# Fuel_Gauge.net
KiCad netlist of a schematic drawn in Altium Designer
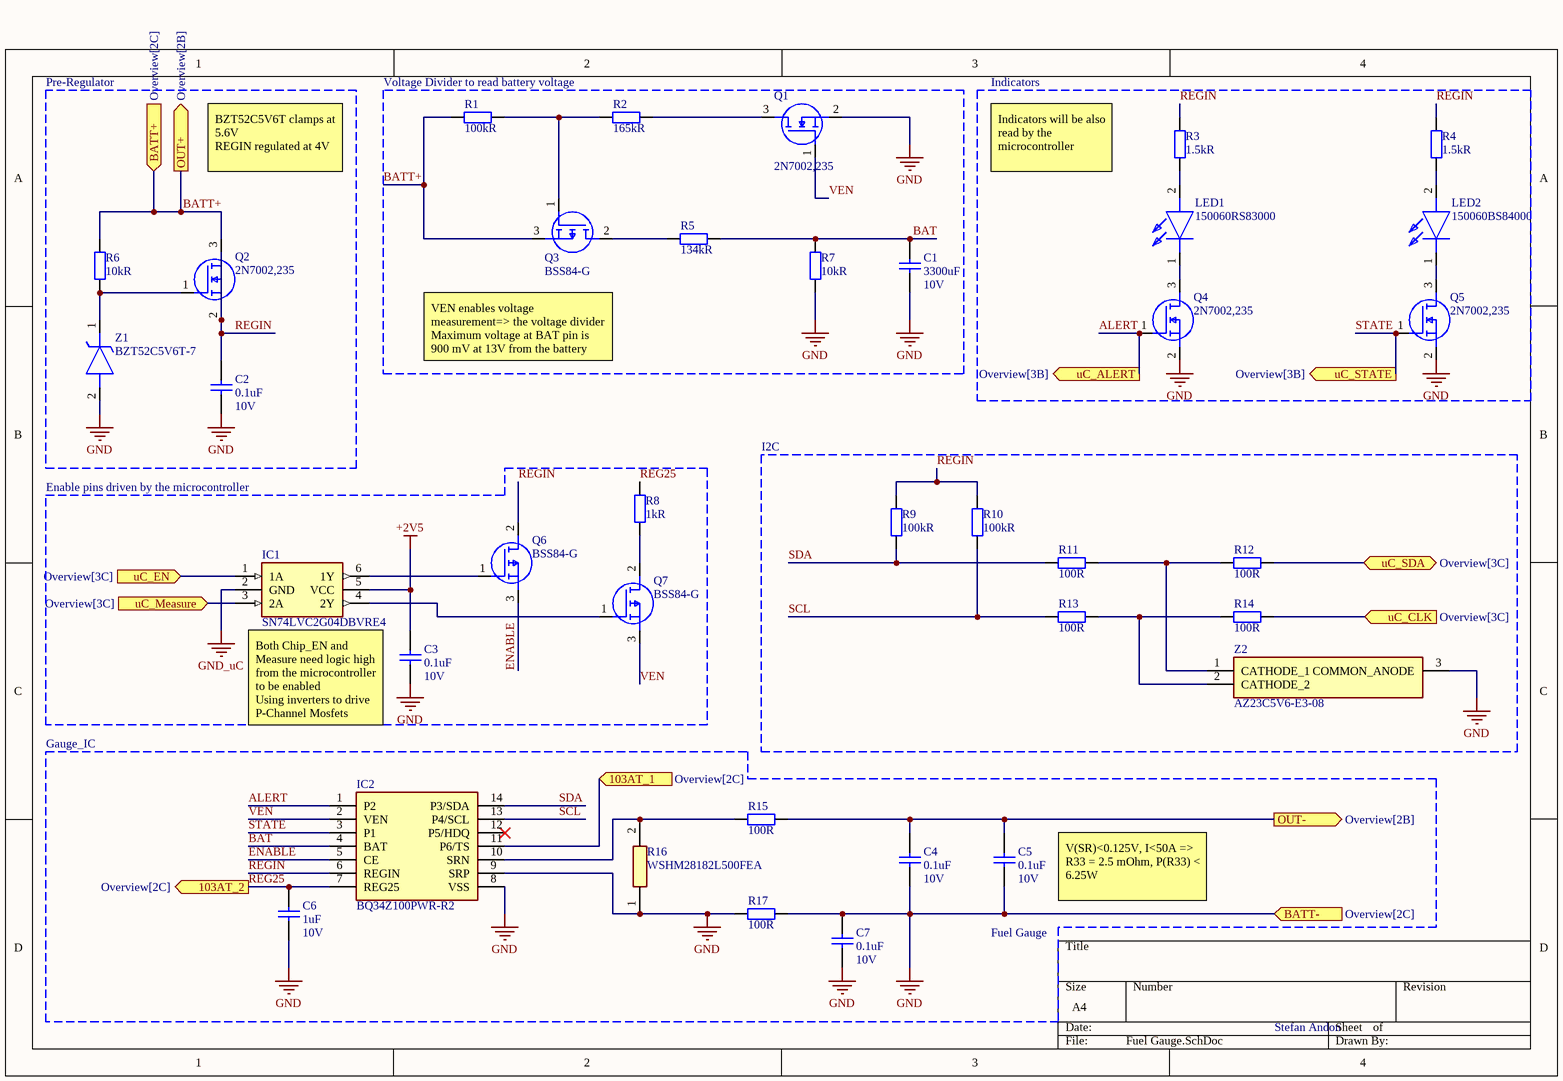
[diagram p0: Fuel Gauge.SchDoc]

(export (version "E")
  (design (tool "Eeschema 10.0.6"))
  (components
    (comp (ref "C1")
      (value "3300uF")
      (footprint "CAP_0603")
      (description "SMD Capacitor")
      (fields
        (field (name "TOLERANCE") "tbd")
        (field (name "VOLTAGE") "10V")
        (field (name "Comment") "Capacitor_SMD")
      )
      (libsource (lib "TUfast e") (part "SMD Capacitor"))
    )
    (comp (ref "C2")
      (value "0.1uF")
      (footprint "CAP_0603")
      (description "SMD Capacitor")
      (fields
        (field (name "TOLERANCE") "tbd")
        (field (name "VOLTAGE") "10V")
        (field (name "Comment") "Capacitor_SMD")
      )
      (libsource (lib "TUfast e") (part "SMD Capacitor"))
    )
    (comp (ref "C3")
      (value "0.1uF")
      (footprint "CAP_0603")
      (description "SMD Capacitor")
      (fields
        (field (name "TOLERANCE") "tbd")
        (field (name "VOLTAGE") "10V")
        (field (name "Comment") "Capacitor_SMD")
      )
      (libsource (lib "TUfast e") (part "SMD Capacitor"))
    )
    (comp (ref "C4")
      (value "0.1uF")
      (footprint "CAP_0603")
      (description "SMD Capacitor")
      (fields
        (field (name "TOLERANCE") "tbd")
        (field (name "VOLTAGE") "10V")
        (field (name "Comment") "Capacitor_SMD")
      )
      (libsource (lib "TUfast e") (part "SMD Capacitor"))
    )
    (comp (ref "C5")
      (value "0.1uF")
      (footprint "CAP_0603")
      (description "SMD Capacitor")
      (fields
        (field (name "TOLERANCE") "tbd")
        (field (name "VOLTAGE") "10V")
        (field (name "Comment") "Capacitor_SMD")
      )
      (libsource (lib "TUfast e") (part "SMD Capacitor"))
    )
    (comp (ref "C6")
      (value "1uF")
      (footprint "CAP_0603")
      (description "SMD Capacitor")
      (fields
        (field (name "TOLERANCE") "tbd")
        (field (name "VOLTAGE") "10V")
        (field (name "Comment") "Capacitor_SMD")
      )
      (libsource (lib "TUfast e") (part "SMD Capacitor"))
    )
    (comp (ref "C7")
      (value "0.1uF")
      (footprint "CAP_0603")
      (description "SMD Capacitor")
      (fields
        (field (name "TOLERANCE") "tbd")
        (field (name "VOLTAGE") "10V")
        (field (name "Comment") "Capacitor_SMD")
      )
      (libsource (lib "TUfast e") (part "SMD Capacitor"))
    )
    (comp (ref "IC1")
      (value "SN74LVC2G04DBVRE4")
      (footprint "SamacSys:SOT95P280X145-6N")
      (description "Integrated Circuit")
      (fields (field (name "MOUSER PART NUMBER") "595-SN74LVC2G04DBVRE"))
      (libsource (lib "*") (part "SN74LVC2G04DBVRE4"))
    )
    (comp (ref "IC2")
      (value "BQ34Z100PWR-R2")
      (footprint "SamacSys:SOP65P640X120-14N")
      (description "Integrated Circuit")
      (fields (field (name "MOUSER PART NUMBER") "595-BQ34Z100PWR-R2"))
      (libsource (lib "*") (part "BQ34Z100PWR-R2"))
    )
    (comp (ref "LED1")
      (value "150060RS83000")
      (footprint "SamacSys:LEDC1608X115N")
      (description "LED")
      (libsource (lib "*") (part "150060RS83000"))
    )
    (comp (ref "LED2")
      (value "150060BS84000")
      (footprint "SamacSys:LEDC1608X105N")
      (description "LED")
      (fields (field (name "MOUSER PART NUMBER") "710-150060BS84000"))
      (libsource (lib "*") (part "150060BS84000"))
    )
    (comp (ref "Q1")
      (value "2N7002,235")
      (footprint "SamacSys:SOT95P230X110-3N")
      (description "MOSFET (N-Channel)")
      (fields (field (name "MOUSER PART NUMBER") "771-2N7002235"))
      (libsource (lib "*") (part "2N7002,235"))
    )
    (comp (ref "Q2")
      (value "2N7002,235")
      (footprint "SamacSys:SOT95P230X110-3N")
      (description "MOSFET (N-Channel)")
      (fields (field (name "MOUSER PART NUMBER") "771-2N7002235"))
      (libsource (lib "*") (part "2N7002,235"))
    )
    (comp (ref "Q3")
      (value "BSS84-G")
      (footprint "SamacSys:SOT95P240X120-3N")
      (description "MOSFET (P-Channel)")
      (fields (field (name "MOUSER PART NUMBER") "863-BSS84-G"))
      (libsource (lib "*") (part "BSS84-G"))
    )
    (comp (ref "Q4")
      (value "2N7002,235")
      (footprint "SamacSys:SOT95P230X110-3N")
      (description "MOSFET (N-Channel)")
      (fields (field (name "MOUSER PART NUMBER") "771-2N7002235"))
      (libsource (lib "*") (part "2N7002,235"))
    )
    (comp (ref "Q5")
      (value "2N7002,235")
      (footprint "SamacSys:SOT95P230X110-3N")
      (description "MOSFET (N-Channel)")
      (fields (field (name "MOUSER PART NUMBER") "771-2N7002235"))
      (libsource (lib "*") (part "2N7002,235"))
    )
    (comp (ref "Q6")
      (value "BSS84-G")
      (footprint "SamacSys:SOT95P240X120-3N")
      (description "MOSFET (P-Channel)")
      (fields (field (name "MOUSER PART NUMBER") "863-BSS84-G"))
      (libsource (lib "*") (part "BSS84-G"))
    )
    (comp (ref "Q7")
      (value "BSS84-G")
      (footprint "SamacSys:SOT95P240X120-3N")
      (description "MOSFET (P-Channel)")
      (fields (field (name "MOUSER PART NUMBER") "863-BSS84-G"))
      (libsource (lib "*") (part "BSS84-G"))
    )
    (comp (ref "R1")
      (value "100kR")
      (footprint "RES_1206")
      (fields
        (field (name "TOLERANCE") "tbd")
        (field (name "POWER") "7W")
        (field (name "Comment") "Resistor_SMD")
      )
      (libsource (lib "TUfast e") (part "Resistor"))
    )
    (comp (ref "R2")
      (value "165kR")
      (footprint "RES_1206")
      (fields
        (field (name "TOLERANCE") "tbd")
        (field (name "POWER") "7W")
        (field (name "Comment") "Resistor_SMD")
      )
      (libsource (lib "TUfast e") (part "Resistor"))
    )
    (comp (ref "R3")
      (value "1.5kR")
      (footprint "RES_1206")
      (fields
        (field (name "TOLERANCE") "tbd")
        (field (name "POWER") "7W")
        (field (name "Comment") "Resistor_SMD")
      )
      (libsource (lib "") (part "Resistor_1"))
    )
    (comp (ref "R4")
      (value "1.5kR")
      (footprint "RES_1206")
      (fields
        (field (name "TOLERANCE") "tbd")
        (field (name "POWER") "7W")
        (field (name "Comment") "Resistor_SMD")
      )
      (libsource (lib "") (part "Resistor_1"))
    )
    (comp (ref "R5")
      (value "134kR")
      (footprint "RES_1206")
      (fields
        (field (name "TOLERANCE") "tbd")
        (field (name "POWER") "7W")
        (field (name "Comment") "Resistor_SMD")
      )
      (libsource (lib "TUfast e") (part "Resistor"))
    )
    (comp (ref "R6")
      (value "10kR")
      (footprint "RES_1206")
      (fields
        (field (name "TOLERANCE") "tbd")
        (field (name "POWER") "7W")
        (field (name "Comment") "Resistor_SMD")
      )
      (libsource (lib "") (part "Resistor_3"))
    )
    (comp (ref "R7")
      (value "10kR")
      (footprint "RES_1206")
      (fields
        (field (name "TOLERANCE") "tbd")
        (field (name "POWER") "7W")
        (field (name "Comment") "Resistor_SMD")
      )
      (libsource (lib "") (part "Resistor_1"))
    )
    (comp (ref "R8")
      (value "1kR")
      (footprint "RES_1206")
      (fields
        (field (name "TOLERANCE") "tbd")
        (field (name "POWER") "7W")
        (field (name "Comment") "Resistor_SMD")
      )
      (libsource (lib "") (part "Resistor_1"))
    )
    (comp (ref "R9")
      (value "100kR")
      (footprint "RES_1206")
      (fields
        (field (name "TOLERANCE") "tbd")
        (field (name "POWER") "7W")
        (field (name "Comment") "Resistor_SMD")
      )
      (libsource (lib "") (part "Resistor_1"))
    )
    (comp (ref "R10")
      (value "100kR")
      (footprint "RES_1206")
      (fields
        (field (name "TOLERANCE") "tbd")
        (field (name "POWER") "7W")
        (field (name "Comment") "Resistor_SMD")
      )
      (libsource (lib "") (part "Resistor_1"))
    )
    (comp (ref "R11")
      (value "100R")
      (footprint "RES_1206")
      (fields
        (field (name "TOLERANCE") "tbd")
        (field (name "POWER") "7W")
        (field (name "Comment") "Resistor_SMD")
      )
      (libsource (lib "") (part "Resistor_2"))
    )
    (comp (ref "R12")
      (value "100R")
      (footprint "RES_1206")
      (fields
        (field (name "TOLERANCE") "tbd")
        (field (name "POWER") "7W")
        (field (name "Comment") "Resistor_SMD")
      )
      (libsource (lib "") (part "Resistor_2"))
    )
    (comp (ref "R13")
      (value "100R")
      (footprint "RES_1206")
      (fields
        (field (name "TOLERANCE") "tbd")
        (field (name "POWER") "7W")
        (field (name "Comment") "Resistor_SMD")
      )
      (libsource (lib "") (part "Resistor_2"))
    )
    (comp (ref "R14")
      (value "100R")
      (footprint "RES_1206")
      (fields
        (field (name "TOLERANCE") "tbd")
        (field (name "POWER") "7W")
        (field (name "Comment") "Resistor_SMD")
      )
      (libsource (lib "") (part "Resistor_2"))
    )
    (comp (ref "R15")
      (value "100R")
      (footprint "RES_1206")
      (fields
        (field (name "TOLERANCE") "tbd")
        (field (name "POWER") "7W")
        (field (name "Comment") "Resistor_SMD")
      )
      (libsource (lib "") (part "Resistor_2"))
    )
    (comp (ref "R16")
      (value "WSHM28182L500FEA")
      (footprint "SamacSys:WSHM28182L500FEA")
      (description "Resistor")
      (fields (field (name "MOUSER PART NUMBER") "71-WSHM28182L500FEA"))
      (libsource (lib "*") (part "WSHM28182L500FEA"))
    )
    (comp (ref "R17")
      (value "100R")
      (footprint "RES_1206")
      (fields
        (field (name "TOLERANCE") "tbd")
        (field (name "POWER") "7W")
        (field (name "Comment") "Resistor_SMD")
      )
      (libsource (lib "") (part "Resistor_2"))
    )
    (comp (ref "Z1")
      (value "BZT52C5V6T-7")
      (footprint "SamacSys:BZT52C5V6T7")
      (description "Zener Diode")
      (fields (field (name "MOUSER PART NUMBER") "621-BZT52C5V6T-7"))
      (libsource (lib "*") (part "BZT52C5V6T-7"))
    )
    (comp (ref "Z2")
      (value "AZ23C5V6-E3-08")
      (footprint "SamacSys:SOT95P248X115-3N")
      (description "Zener Diode")
      (fields (field (name "MOUSER PART NUMBER") "78-AZ23C5V6-E3-08"))
      (libsource (lib "*") (part "AZ23C5V6-E3-08"))
    )
  )
  (nets
    (net (code "1") (name "+2V5") (class "Default")
      (node (ref "C3") (pin "2") (pinfunction "2_2") (pintype "passive"))
      (node (ref "IC1") (pin "5") (pinfunction "VCC_5") (pintype "power_in"))
    )
    (net (code "2") (name "/103AT_1") (class "Default")
      (node (ref "IC2") (pin "11") (pinfunction "P6/TS_11") (pintype "passive"))
    )
    (net (code "3") (name "/ALERT") (class "Default")
      (node (ref "IC2") (pin "1") (pinfunction "P2_1") (pintype "passive"))
      (node (ref "Q4") (pin "1") (pinfunction "G_1") (pintype "passive"))
    )
    (net (code "4") (name "/BAT") (class "Default")
      (node (ref "C1") (pin "2") (pinfunction "2_2") (pintype "passive"))
      (node (ref "IC2") (pin "4") (pinfunction "BAT_4") (pintype "passive"))
      (node (ref "R5") (pin "2") (pinfunction "2_2") (pintype "passive"))
      (node (ref "R7") (pin "2") (pinfunction "2_2") (pintype "passive"))
    )
    (net (code "5") (name "/BATT+") (class "Default")
      (node (ref "Q2") (pin "3") (pinfunction "D_3") (pintype "passive"))
      (node (ref "Q3") (pin "3") (pinfunction "S_3") (pintype "passive"))
      (node (ref "R1") (pin "1") (pinfunction "1_1") (pintype "passive"))
      (node (ref "R6") (pin "1") (pinfunction "1_1") (pintype "passive"))
    )
    (net (code "6") (name "/ENABLE") (class "Default")
      (node (ref "IC2") (pin "5") (pinfunction "CE_5") (pintype "passive"))
      (node (ref "Q6") (pin "3") (pinfunction "S_3") (pintype "passive"))
    )
    (net (code "7") (name "/OUT-") (class "Default")
      (node (ref "C4") (pin "2") (pinfunction "2_2") (pintype "passive"))
      (node (ref "C5") (pin "2") (pinfunction "2_2") (pintype "passive"))
      (node (ref "R15") (pin "1") (pinfunction "1_1") (pintype "passive"))
    )
    (net (code "8") (name "/REG25") (class "Default")
      (node (ref "C6") (pin "2") (pinfunction "2_2") (pintype "passive"))
      (node (ref "IC2") (pin "7") (pinfunction "REG25_7") (pintype "passive"))
      (node (ref "R8") (pin "2") (pinfunction "2_2") (pintype "passive"))
    )
    (net (code "9") (name "/REGIN") (class "Default")
      (node (ref "C2") (pin "2") (pinfunction "2_2") (pintype "passive"))
      (node (ref "IC2") (pin "6") (pinfunction "REGIN_6") (pintype "passive"))
      (node (ref "Q2") (pin "2") (pinfunction "S_2") (pintype "passive"))
      (node (ref "Q6") (pin "2") (pinfunction "D_2") (pintype "passive"))
      (node (ref "R10") (pin "2") (pinfunction "2_2") (pintype "passive"))
      (node (ref "R3") (pin "2") (pinfunction "2_2") (pintype "passive"))
      (node (ref "R4") (pin "2") (pinfunction "2_2") (pintype "passive"))
      (node (ref "R9") (pin "2") (pinfunction "2_2") (pintype "passive"))
    )
    (net (code "10") (name "/SCL") (class "Default")
      (node (ref "IC2") (pin "13") (pinfunction "P4/SCL_13") (pintype "passive"))
      (node (ref "R10") (pin "1") (pinfunction "1_1") (pintype "passive"))
      (node (ref "R13") (pin "2") (pinfunction "2_2") (pintype "passive"))
    )
    (net (code "11") (name "/SDA") (class "Default")
      (node (ref "IC2") (pin "14") (pinfunction "P3/SDA_14") (pintype "passive"))
      (node (ref "R11") (pin "2") (pinfunction "2_2") (pintype "passive"))
      (node (ref "R9") (pin "1") (pinfunction "1_1") (pintype "passive"))
    )
    (net (code "12") (name "/STATE") (class "Default")
      (node (ref "IC2") (pin "3") (pinfunction "P1_3") (pintype "passive"))
      (node (ref "Q5") (pin "1") (pinfunction "G_1") (pintype "passive"))
    )
    (net (code "13") (name "/VEN") (class "Default")
      (node (ref "IC2") (pin "2") (pinfunction "VEN_2") (pintype "passive"))
      (node (ref "Q1") (pin "1") (pinfunction "G_1") (pintype "passive"))
      (node (ref "Q7") (pin "3") (pinfunction "S_3") (pintype "passive"))
    )
    (net (code "14") (name "/uC_CLK") (class "Default")
      (node (ref "R14") (pin "1") (pinfunction "1_1") (pintype "passive"))
    )
    (net (code "15") (name "/uC_EN") (class "Default")
      (node (ref "IC1") (pin "1") (pinfunction "1A_1") (pintype "input"))
    )
    (net (code "16") (name "/uC_Measure") (class "Default")
      (node (ref "IC1") (pin "3") (pinfunction "2A_3") (pintype "input"))
    )
    (net (code "17") (name "/uC_SDA") (class "Default")
      (node (ref "R12") (pin "1") (pinfunction "1_1") (pintype "passive"))
    )
    (net (code "18") (name "GND") (class "Default")
      (node (ref "C1") (pin "1") (pinfunction "1_1") (pintype "passive"))
      (node (ref "C2") (pin "1") (pinfunction "1_1") (pintype "passive"))
      (node (ref "C3") (pin "1") (pinfunction "1_1") (pintype "passive"))
      (node (ref "C4") (pin "1") (pinfunction "1_1") (pintype "passive"))
      (node (ref "C5") (pin "1") (pinfunction "1_1") (pintype "passive"))
      (node (ref "C6") (pin "1") (pinfunction "1_1") (pintype "passive"))
      (node (ref "C7") (pin "1") (pinfunction "1_1") (pintype "passive"))
      (node (ref "C7") (pin "2") (pinfunction "2_2") (pintype "passive"))
      (node (ref "IC2") (pin "8") (pinfunction "VSS_8") (pintype "passive"))
      (node (ref "IC2") (pin "9") (pinfunction "SRP_9") (pintype "passive"))
      (node (ref "Q1") (pin "2") (pinfunction "S_2") (pintype "passive"))
      (node (ref "Q4") (pin "2") (pinfunction "S_2") (pintype "passive"))
      (node (ref "Q5") (pin "2") (pinfunction "S_2") (pintype "passive"))
      (node (ref "R16") (pin "1") (pinfunction "1_1") (pintype "passive"))
      (node (ref "R17") (pin "1") (pinfunction "1_1") (pintype "passive"))
      (node (ref "R17") (pin "2") (pinfunction "2_2") (pintype "passive"))
      (node (ref "R7") (pin "1") (pinfunction "1_1") (pintype "passive"))
      (node (ref "Z1") (pin "2") (pinfunction "A_2") (pintype "passive"))
      (node (ref "Z2") (pin "3") (pinfunction "COMMON_ANODE_3") (pintype "passive"))
    )
    (net (code "19") (name "GND_uC") (class "Default")
      (node (ref "IC1") (pin "2") (pinfunction "GND_2") (pintype "power_in"))
    )
    (net (code "20") (name "Net-(IC1-1Y)") (class "Default")
      (node (ref "IC1") (pin "6") (pinfunction "1Y_6") (pintype "output"))
      (node (ref "Q6") (pin "1") (pinfunction "G_1") (pintype "passive"))
    )
    (net (code "21") (name "Net-(IC1-2Y)") (class "Default")
      (node (ref "IC1") (pin "4") (pinfunction "2Y_4") (pintype "output"))
      (node (ref "Q7") (pin "1") (pinfunction "G_1") (pintype "passive"))
    )
    (net (code "22") (name "Net-(IC2-SRN)") (class "Default")
      (node (ref "IC2") (pin "10") (pinfunction "SRN_10") (pintype "passive"))
      (node (ref "R15") (pin "2") (pinfunction "2_2") (pintype "passive"))
      (node (ref "R16") (pin "2") (pinfunction "2_2") (pintype "passive"))
    )
    (net (code "23") (name "Net-(LED1-A)") (class "Default")
      (node (ref "LED1") (pin "2") (pinfunction "A_2") (pintype "passive"))
      (node (ref "R3") (pin "1") (pinfunction "1_1") (pintype "passive"))
    )
    (net (code "24") (name "Net-(LED1-K)") (class "Default")
      (node (ref "LED1") (pin "1") (pinfunction "K_1") (pintype "passive"))
      (node (ref "Q4") (pin "3") (pinfunction "D_3") (pintype "passive"))
    )
    (net (code "25") (name "Net-(LED2-A)") (class "Default")
      (node (ref "LED2") (pin "2") (pinfunction "A_2") (pintype "passive"))
      (node (ref "R4") (pin "1") (pinfunction "1_1") (pintype "passive"))
    )
    (net (code "26") (name "Net-(LED2-K)") (class "Default")
      (node (ref "LED2") (pin "1") (pinfunction "K_1") (pintype "passive"))
      (node (ref "Q5") (pin "3") (pinfunction "D_3") (pintype "passive"))
    )
    (net (code "27") (name "Net-(Q1-D)") (class "Default")
      (node (ref "Q1") (pin "3") (pinfunction "D_3") (pintype "passive"))
      (node (ref "R2") (pin "2") (pinfunction "2_2") (pintype "passive"))
    )
    (net (code "28") (name "Net-(Q2-G)") (class "Default")
      (node (ref "Q2") (pin "1") (pinfunction "G_1") (pintype "passive"))
      (node (ref "R6") (pin "2") (pinfunction "2_2") (pintype "passive"))
      (node (ref "Z1") (pin "1") (pinfunction "K_1") (pintype "passive"))
    )
    (net (code "29") (name "Net-(Q3-D)") (class "Default")
      (node (ref "Q3") (pin "2") (pinfunction "D_2") (pintype "passive"))
      (node (ref "R5") (pin "1") (pinfunction "1_1") (pintype "passive"))
    )
    (net (code "30") (name "Net-(Q3-G)") (class "Default")
      (node (ref "Q3") (pin "1") (pinfunction "G_1") (pintype "passive"))
      (node (ref "R1") (pin "2") (pinfunction "2_2") (pintype "passive"))
      (node (ref "R2") (pin "1") (pinfunction "1_1") (pintype "passive"))
    )
    (net (code "31") (name "Net-(Q7-D)") (class "Default")
      (node (ref "Q7") (pin "2") (pinfunction "D_2") (pintype "passive"))
      (node (ref "R8") (pin "1") (pinfunction "1_1") (pintype "passive"))
    )
    (net (code "32") (name "Net-(Z2-CATHODE_1)") (class "Default")
      (node (ref "R11") (pin "1") (pinfunction "1_1") (pintype "passive"))
      (node (ref "R12") (pin "2") (pinfunction "2_2") (pintype "passive"))
      (node (ref "Z2") (pin "1") (pinfunction "CATHODE_1_1") (pintype "passive"))
    )
    (net (code "33") (name "Net-(Z2-CATHODE_2)") (class "Default")
      (node (ref "R13") (pin "1") (pinfunction "1_1") (pintype "passive"))
      (node (ref "R14") (pin "2") (pinfunction "2_2") (pintype "passive"))
      (node (ref "Z2") (pin "2") (pinfunction "CATHODE_2_2") (pintype "passive"))
    )
    (net (code "34") (name "unconnected-(IC2-P5{slash}HDQ-Pad12)") (class "Default")
      (node (ref "IC2") (pin "12") (pinfunction "P5/HDQ_12") (pintype "passive+no_connect"))
    )
  )
)
